# A4a_Pro_Mini.net
KiCad netlist of a schematic drawn in EAGLE
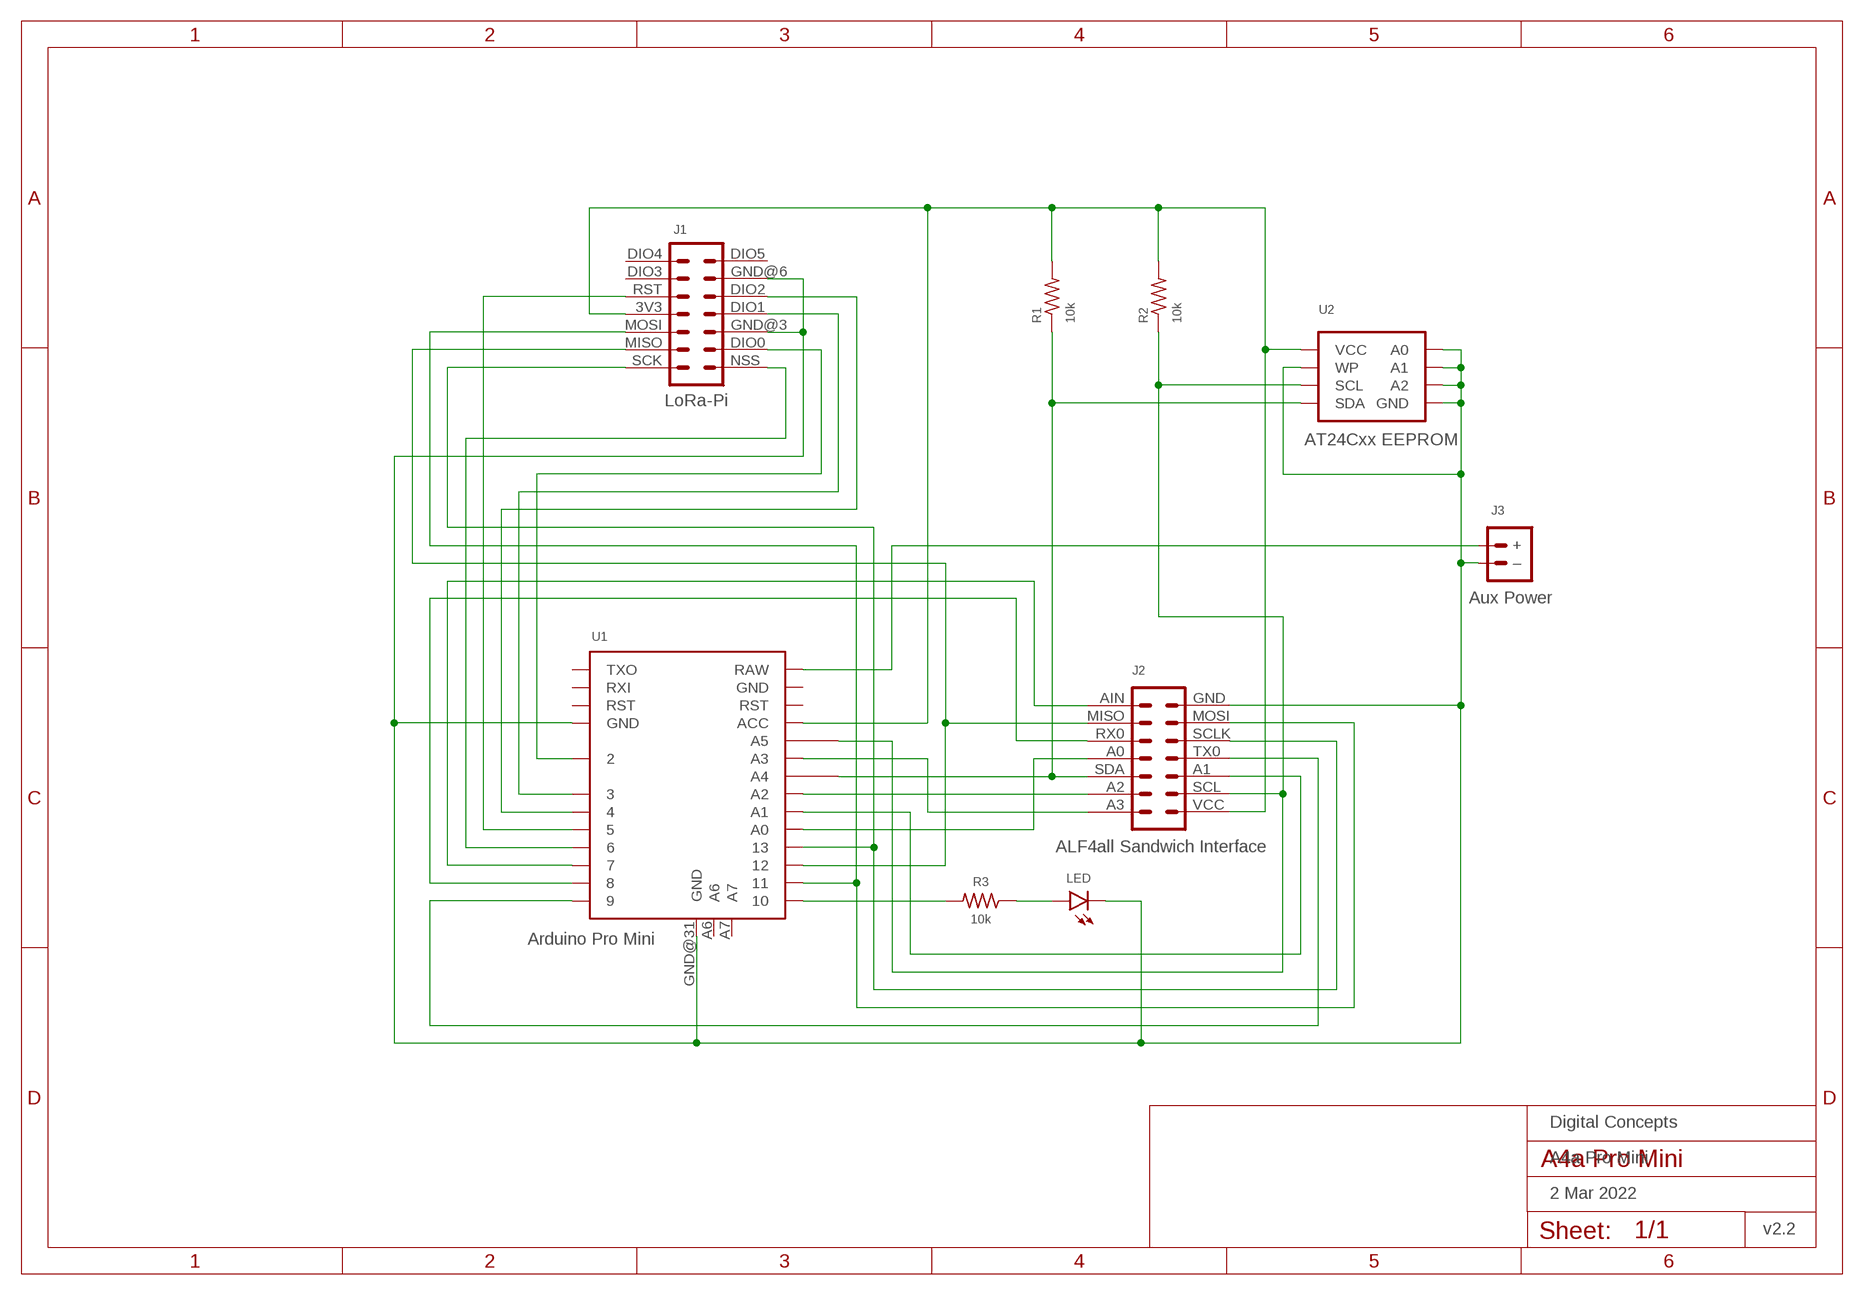
[diagram p0: schematic, sheet 1]

(export (version "E")
  (design (tool "Eeschema 10.0.6"))
  (components
    (comp (ref "J1")
      (value "LoRa-Pi")
      (footprint "eagle-import:RFM95W-PI")
      (libsource (lib "eagle-import") (part "RFM95W-PI-HEADER"))
    )
    (comp (ref "J2")
      (value "ALF4all Sandwich Interface")
      (footprint "eagle-import:CONN_2X7-ALF4ALL-PROCESSOR-B")
      (libsource (lib "eagle-import") (part "HEADER-2X7-ALF4ALL-PROCESSOR-B"))
    )
    (comp (ref "J3")
      (value "Aux Power")
      (footprint "eagle-import:JST-PH2.0-2-HORIZONTAL")
      (libsource (lib "eagle-import") (part "JST-PH2.0-2-MALE-HORIZONTALJST-PTH-2"))
    )
    (comp (ref "LED")
      (value "LEDCHIP-LED0805")
      (footprint "eagle-import:CHIP-LED0805")
      (libsource (lib "eagle-import") (part "LEDCHIP-LED0805"))
    )
    (comp (ref "R1")
      (value "10k")
      (footprint "eagle-import:R0805")
      (libsource (lib "eagle-import") (part "RESISTORR0805"))
    )
    (comp (ref "R2")
      (value "10k")
      (footprint "eagle-import:R0805")
      (libsource (lib "eagle-import") (part "RESISTORR0805"))
    )
    (comp (ref "R3")
      (value "10k")
      (footprint "eagle-import:R0805")
      (libsource (lib "eagle-import") (part "RESISTORR0805"))
    )
    (comp (ref "U1")
      (value "Arduino Pro Mini")
      (footprint "eagle-import:ARDUINO-PRO-MINI-35")
      (libsource (lib "eagle-import") (part "ARDUINO-PRO-MINI-35"))
    )
    (comp (ref "U2")
      (value "AT24Cxx EEPROM")
      (footprint "eagle-import:SOP-8")
      (libsource (lib "eagle-import") (part "AT24CXX-EEPROM"))
    )
  )
  (nets
    (net (code "1") (name "Net-(J1-1)") (class "Default")
      (node (ref "J1") (pin "NSS") (pinfunction "1_NSS") (pintype "passive"))
      (node (ref "U1") (pin "6") (pinfunction "6_6") (pintype "bidirectional"))
    )
    (net (code "2") (name "Net-(J1-2)") (class "Default")
      (node (ref "J1") (pin "DIO0") (pinfunction "2_DIO0") (pintype "passive"))
      (node (ref "U1") (pin "2") (pinfunction "2_2") (pintype "bidirectional"))
    )
    (net (code "3") (name "Net-(J1-3)") (class "Default")
      (node (ref "J1") (pin "GND@3") (pinfunction "3_GND@3") (pintype "passive"))
      (node (ref "J1") (pin "GND@6") (pinfunction "6_GND@6") (pintype "passive"))
      (node (ref "J2") (pin "GND") (pinfunction "7_GND") (pintype "passive"))
      (node (ref "J3") (pin "-") (pinfunction "–_-") (pintype "power_in"))
      (node (ref "LED") (pin "C") (pinfunction "C_C") (pintype "passive"))
      (node (ref "U1") (pin "GND@22") (pinfunction "GND_GND@22") (pintype "bidirectional"))
      (node (ref "U1") (pin "GND@31") (pinfunction "GND_GND@31") (pintype "bidirectional"))
      (node (ref "U2") (pin "P$1") (pinfunction "A0_P$1") (pintype "bidirectional"))
      (node (ref "U2") (pin "P$2") (pinfunction "A1_P$2") (pintype "bidirectional"))
      (node (ref "U2") (pin "P$3") (pinfunction "A2_P$3") (pintype "bidirectional"))
      (node (ref "U2") (pin "P$4") (pinfunction "GND_P$4") (pintype "bidirectional"))
      (node (ref "U2") (pin "P$7") (pinfunction "WP_P$7") (pintype "bidirectional"))
    )
    (net (code "4") (name "Net-(J1-4)") (class "Default")
      (node (ref "J1") (pin "DIO1") (pinfunction "4_DIO1") (pintype "passive"))
      (node (ref "U1") (pin "3") (pinfunction "3_3") (pintype "bidirectional"))
    )
    (net (code "5") (name "Net-(J1-5)") (class "Default")
      (node (ref "J1") (pin "DIO2") (pinfunction "5_DIO2") (pintype "passive"))
      (node (ref "U1") (pin "4") (pinfunction "4_4") (pintype "bidirectional"))
    )
    (net (code "6") (name "Net-(J1-10)") (class "Default")
      (node (ref "J1") (pin "RST") (pinfunction "10_RST") (pintype "passive"))
      (node (ref "U1") (pin "5") (pinfunction "5_5") (pintype "bidirectional"))
    )
    (net (code "7") (name "Net-(J1-11)") (class "Default")
      (node (ref "J1") (pin "3V3") (pinfunction "11_3V3") (pintype "passive"))
      (node (ref "J2") (pin "VCC") (pinfunction "1_VCC") (pintype "passive"))
      (node (ref "R1") (pin "2") (pinfunction "2_2") (pintype "passive"))
      (node (ref "R2") (pin "2") (pinfunction "2_2") (pintype "passive"))
      (node (ref "U1") (pin "ACC") (pinfunction "ACC_ACC") (pintype "bidirectional"))
      (node (ref "U2") (pin "P$8") (pinfunction "VCC_P$8") (pintype "bidirectional"))
    )
    (net (code "8") (name "Net-(J1-12)") (class "Default")
      (node (ref "J1") (pin "MOSI") (pinfunction "12_MOSI") (pintype "passive"))
      (node (ref "J2") (pin "MOSI") (pinfunction "6_MOSI") (pintype "passive"))
      (node (ref "U1") (pin "11") (pinfunction "11_11") (pintype "bidirectional"))
    )
    (net (code "9") (name "Net-(J1-13)") (class "Default")
      (node (ref "J1") (pin "MISO") (pinfunction "13_MISO") (pintype "passive"))
      (node (ref "J2") (pin "MISO") (pinfunction "9_MISO") (pintype "passive"))
      (node (ref "U1") (pin "12") (pinfunction "12_12") (pintype "bidirectional"))
    )
    (net (code "10") (name "Net-(J1-14)") (class "Default")
      (node (ref "J1") (pin "SCK") (pinfunction "14_SCK") (pintype "passive"))
      (node (ref "J2") (pin "SCLK") (pinfunction "5_SCLK") (pintype "passive"))
      (node (ref "U1") (pin "13") (pinfunction "13_13") (pintype "bidirectional"))
    )
    (net (code "11") (name "Net-(J2-2)") (class "Default")
      (node (ref "J2") (pin "SCL") (pinfunction "2_SCL") (pintype "passive"))
      (node (ref "R2") (pin "1") (pinfunction "1_1") (pintype "passive"))
      (node (ref "U1") (pin "A5") (pinfunction "A5_A5") (pintype "bidirectional"))
      (node (ref "U2") (pin "P$6") (pinfunction "SCL_P$6") (pintype "bidirectional"))
    )
    (net (code "12") (name "Net-(J2-3)") (class "Default")
      (node (ref "J2") (pin "A1") (pinfunction "3_A1") (pintype "passive"))
      (node (ref "U1") (pin "A1") (pinfunction "A1_A1") (pintype "bidirectional"))
    )
    (net (code "13") (name "Net-(J2-4)") (class "Default")
      (node (ref "J2") (pin "TX0") (pinfunction "4_TX0") (pintype "passive"))
      (node (ref "U1") (pin "9") (pinfunction "9_9") (pintype "bidirectional"))
    )
    (net (code "14") (name "Net-(J2-8)") (class "Default")
      (node (ref "J2") (pin "AIN") (pinfunction "8_AIN") (pintype "passive"))
      (node (ref "U1") (pin "7") (pinfunction "7_7") (pintype "bidirectional"))
    )
    (net (code "15") (name "Net-(J2-10)") (class "Default")
      (node (ref "J2") (pin "RX0") (pinfunction "10_RX0") (pintype "passive"))
      (node (ref "U1") (pin "8") (pinfunction "8_8") (pintype "bidirectional"))
    )
    (net (code "16") (name "Net-(J2-11)") (class "Default")
      (node (ref "J2") (pin "A0") (pinfunction "11_A0") (pintype "passive"))
      (node (ref "U1") (pin "A0") (pinfunction "A0_A0") (pintype "bidirectional"))
    )
    (net (code "17") (name "Net-(J2-12)") (class "Default")
      (node (ref "J2") (pin "SDA") (pinfunction "12_SDA") (pintype "passive"))
      (node (ref "R1") (pin "1") (pinfunction "1_1") (pintype "passive"))
      (node (ref "U1") (pin "A4") (pinfunction "A4_A4") (pintype "bidirectional"))
      (node (ref "U2") (pin "P$5") (pinfunction "SDA_P$5") (pintype "bidirectional"))
    )
    (net (code "18") (name "Net-(J2-13)") (class "Default")
      (node (ref "J2") (pin "A2") (pinfunction "13_A2") (pintype "passive"))
      (node (ref "U1") (pin "A2") (pinfunction "A2_A2") (pintype "bidirectional"))
    )
    (net (code "19") (name "Net-(J2-14)") (class "Default")
      (node (ref "J2") (pin "A3") (pinfunction "14_A3") (pintype "passive"))
      (node (ref "U1") (pin "A3") (pinfunction "A3_A3") (pintype "bidirectional"))
    )
    (net (code "20") (name "Net-(J3-Pad+)") (class "Default")
      (node (ref "J3") (pin "+") (pinfunction "+_+") (pintype "power_in"))
      (node (ref "U1") (pin "RAW") (pinfunction "RAW_RAW") (pintype "bidirectional"))
    )
    (net (code "21") (name "Net-(LED-PadA)") (class "Default")
      (node (ref "LED") (pin "A") (pinfunction "A_A") (pintype "passive"))
      (node (ref "R3") (pin "1") (pinfunction "1_1") (pintype "passive"))
    )
    (net (code "22") (name "Net-(R3-Pad2)") (class "Default")
      (node (ref "R3") (pin "2") (pinfunction "2_2") (pintype "passive"))
      (node (ref "U1") (pin "10") (pinfunction "10_10") (pintype "bidirectional"))
    )
    (net (code "23") (name "unconnected-(J1-7-PadDIO5)") (class "Default")
      (node (ref "J1") (pin "DIO5") (pinfunction "7_DIO5") (pintype "passive"))
    )
    (net (code "24") (name "unconnected-(J1-8-PadDIO4)") (class "Default")
      (node (ref "J1") (pin "DIO4") (pinfunction "8_DIO4") (pintype "passive"))
    )
    (net (code "25") (name "unconnected-(J1-9-PadDIO3)") (class "Default")
      (node (ref "J1") (pin "DIO3") (pinfunction "9_DIO3") (pintype "passive"))
    )
    (net (code "26") (name "unconnected-(U1-GND-PadGND@11)") (class "Default")
      (node (ref "U1") (pin "GND@11") (pinfunction "GND_GND@11") (pintype "bidirectional"))
    )
    (net (code "27") (name "unconnected-(U1-PadA6)") (class "Default")
      (node (ref "U1") (pin "A6") (pinfunction "A6_A6") (pintype "bidirectional"))
    )
    (net (code "28") (name "unconnected-(U1-PadA7)") (class "Default")
      (node (ref "U1") (pin "A7") (pinfunction "A7_A7") (pintype "bidirectional"))
    )
    (net (code "29") (name "unconnected-(U1-RST-PadRST@10)") (class "Default")
      (node (ref "U1") (pin "RST@10") (pinfunction "RST_RST@10") (pintype "bidirectional"))
    )
    (net (code "30") (name "unconnected-(U1-RST-PadRST@21)") (class "Default")
      (node (ref "U1") (pin "RST@21") (pinfunction "RST_RST@21") (pintype "bidirectional"))
    )
    (net (code "31") (name "unconnected-(U1-RXI-PadRXI@20)") (class "Default")
      (node (ref "U1") (pin "RXI@20") (pinfunction "RXI_RXI@20") (pintype "bidirectional"))
    )
    (net (code "32") (name "unconnected-(U1-TXO-PadTXO@19)") (class "Default")
      (node (ref "U1") (pin "TXO@19") (pinfunction "TXO_TXO@19") (pintype "bidirectional"))
    )
  )
)
